# Fuente.net
KiCad netlist of a schematic drawn in EAGLE
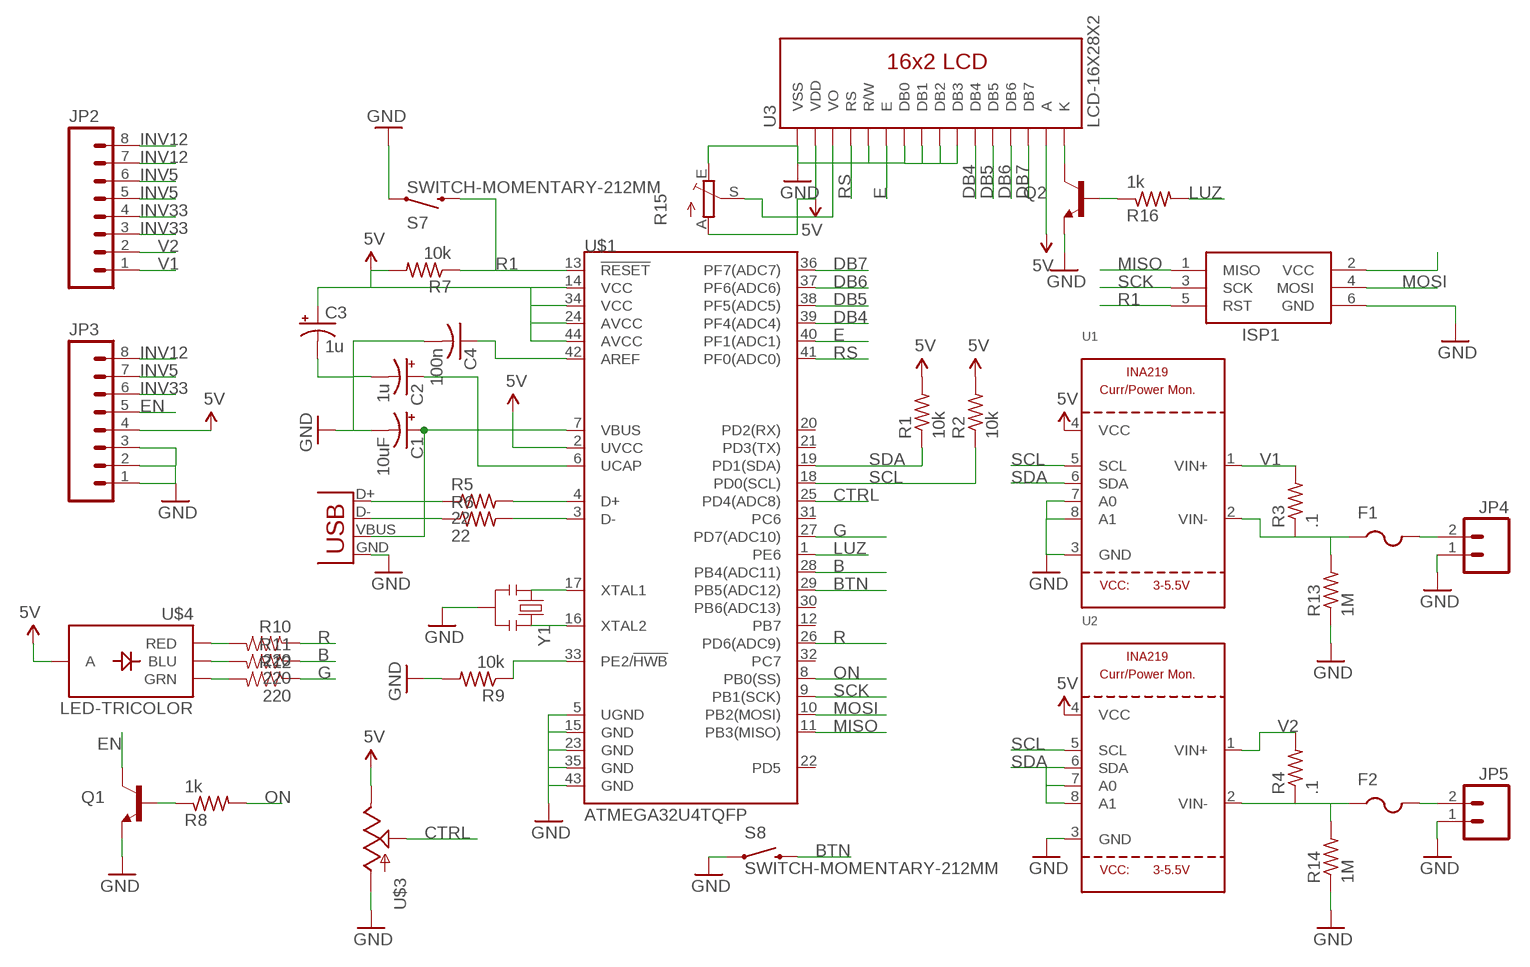
[diagram p0: schematic, sheet 1]

(export (version "E")
  (design (tool "Eeschema 10.0.6"))
  (components
    (comp (ref "C1")
      (value "10uF")
      (footprint "eagle-import:CPOL-RADIAL-10UF-25V")
      (libsource (lib "eagle-import") (part "CAP_POLPTH2"))
    )
    (comp (ref "C2")
      (value "1u")
      (footprint "eagle-import:E2,5-6")
      (libsource (lib "eagle-import") (part "CPOL-USE2.5-6"))
    )
    (comp (ref "C3")
      (value "1u")
      (footprint "eagle-import:E2,5-6")
      (libsource (lib "eagle-import") (part "CPOL-USE2.5-6"))
    )
    (comp (ref "C4")
      (value "100n")
      (footprint "eagle-import:C0805K")
      (libsource (lib "eagle-import") (part "C-USC0805K"))
    )
    (comp (ref "F1")
      (value "PTCFUSE-1812")
      (footprint "eagle-import:1812")
      (libsource (lib "eagle-import") (part "PTCFUSE-1812"))
    )
    (comp (ref "F2")
      (value "PTCFUSE-1812")
      (footprint "eagle-import:1812")
      (libsource (lib "eagle-import") (part "PTCFUSE-1812"))
    )
    (comp (ref "ISP1")
      (value "AVRISP-6")
      (footprint "eagle-import:AVRISP")
      (libsource (lib "eagle-import") (part "AVRISP-6"))
    )
    (comp (ref "JP1")
      (value "USBSMD")
      (footprint "eagle-import:USB-MINIB")
      (libsource (lib "eagle-import") (part "USBSMD"))
    )
    (comp (ref "JP2")
      (value "M08LONGPADS")
      (footprint "eagle-import:1X08_LONGPADS")
      (libsource (lib "eagle-import") (part "M08LONGPADS"))
    )
    (comp (ref "JP3")
      (value "M08LONGPADS")
      (footprint "eagle-import:1X08_LONGPADS")
      (libsource (lib "eagle-import") (part "M08LONGPADS"))
    )
    (comp (ref "JP4")
      (value "M02LOCK_LONGPADS")
      (footprint "eagle-import:1X02_LOCK_LONGPADS")
      (libsource (lib "eagle-import") (part "M02LOCK_LONGPADS"))
    )
    (comp (ref "JP5")
      (value "M02LOCK_LONGPADS")
      (footprint "eagle-import:1X02_LOCK_LONGPADS")
      (libsource (lib "eagle-import") (part "M02LOCK_LONGPADS"))
    )
    (comp (ref "Q1")
      (value "TRANSISTOR_NPNSOT23")
      (footprint "eagle-import:SOT23")
      (libsource (lib "eagle-import") (part "TRANSISTOR_NPNSOT23"))
    )
    (comp (ref "Q2")
      (value "TRANSISTOR_NPNSOT23")
      (footprint "eagle-import:SOT23")
      (libsource (lib "eagle-import") (part "TRANSISTOR_NPNSOT23"))
    )
    (comp (ref "R1")
      (value "10k")
      (footprint "eagle-import:M0805")
      (libsource (lib "eagle-import") (part "R-US_M0805"))
    )
    (comp (ref "R2")
      (value "10k")
      (footprint "eagle-import:M0805")
      (libsource (lib "eagle-import") (part "R-US_M0805"))
    )
    (comp (ref "R3")
      (value ".1")
      (footprint "eagle-import:R2512")
      (libsource (lib "eagle-import") (part "R-US_R2512"))
    )
    (comp (ref "R4")
      (value ".1")
      (footprint "eagle-import:R2512")
      (libsource (lib "eagle-import") (part "R-US_R2512"))
    )
    (comp (ref "R5")
      (value "22")
      (footprint "eagle-import:0309_12")
      (libsource (lib "eagle-import") (part "R-US_0309/12"))
    )
    (comp (ref "R6")
      (value "22")
      (footprint "eagle-import:0309_12")
      (libsource (lib "eagle-import") (part "R-US_0309/12"))
    )
    (comp (ref "R7")
      (value "10k")
      (footprint "eagle-import:M0805")
      (libsource (lib "eagle-import") (part "R-US_M0805"))
    )
    (comp (ref "R8")
      (value "1k")
      (footprint "eagle-import:M0805")
      (libsource (lib "eagle-import") (part "R-US_M0805"))
    )
    (comp (ref "R9")
      (value "10k")
      (footprint "eagle-import:M0805")
      (libsource (lib "eagle-import") (part "R-US_M0805"))
    )
    (comp (ref "R10")
      (value "220")
      (footprint "eagle-import:0805")
      (libsource (lib "eagle-import") (part "RESISTOR0805-RES"))
    )
    (comp (ref "R11")
      (value "220")
      (footprint "eagle-import:0805")
      (libsource (lib "eagle-import") (part "RESISTOR0805-RES"))
    )
    (comp (ref "R12")
      (value "220")
      (footprint "eagle-import:0805")
      (libsource (lib "eagle-import") (part "RESISTOR0805-RES"))
    )
    (comp (ref "R13")
      (value "1M")
      (footprint "eagle-import:M0805")
      (libsource (lib "eagle-import") (part "R-US_M0805"))
    )
    (comp (ref "R14")
      (value "1M")
      (footprint "eagle-import:M0805")
      (libsource (lib "eagle-import") (part "R-US_M0805"))
    )
    (comp (ref "R15")
      (value "TRIM_EU-CT6")
      (footprint "eagle-import:CT6")
      (libsource (lib "eagle-import") (part "TRIM_EU-CT6"))
    )
    (comp (ref "R16")
      (value "1k")
      (footprint "eagle-import:M0805")
      (libsource (lib "eagle-import") (part "R-US_M0805"))
    )
    (comp (ref "S7")
      (value "SWITCH-MOMENTARY-212MM")
      (footprint "eagle-import:TACTILE-PTH-12MM")
      (libsource (lib "eagle-import") (part "SWITCH-MOMENTARY-212MM"))
    )
    (comp (ref "S8")
      (value "SWITCH-MOMENTARY-212MM")
      (footprint "eagle-import:TACTILE-PTH-12MM")
      (libsource (lib "eagle-import") (part "SWITCH-MOMENTARY-212MM"))
    )
    (comp (ref "U$1")
      (value "ATMEGA32U4TQFP")
      (footprint "eagle-import:SPARKFUN-DIGITALIC_TQFP44")
      (libsource (lib "eagle-import") (part "ATMEGA32U4TQFP"))
    )
    (comp (ref "U$3")
      (value "POT-RV16AF-20")
      (footprint "eagle-import:POT_ALPHA_RV16AF-20")
      (libsource (lib "eagle-import") (part "POT-RV16AF-20"))
    )
    (comp (ref "U$4")
      (value "LED-TRICOLOR")
      (footprint "eagle-import:LED-TRICOLOR-SMD")
      (libsource (lib "eagle-import") (part "LED-TRICOLOR"))
    )
    (comp (ref "U1")
      (value "INA219")
      (footprint "eagle-import:SOT23-8")
      (libsource (lib "eagle-import") (part "INA219"))
    )
    (comp (ref "U2")
      (value "INA219")
      (footprint "eagle-import:SOT23-8")
      (libsource (lib "eagle-import") (part "INA219"))
    )
    (comp (ref "U3")
      (value "LCD-16X28X2")
      (footprint "eagle-import:LCD-8X2")
      (libsource (lib "eagle-import") (part "LCD-16X28X2"))
    )
    (comp (ref "Y1")
      (value "RESONATORPTH")
      (footprint "eagle-import:RESONATOR-PTH")
      (libsource (lib "eagle-import") (part "RESONATORPTH"))
    )
  )
  (nets
    (net (code "1") (name "/B") (class "Default")
      (node (ref "R11") (pin "1") (pinfunction "1_1") (pintype "passive"))
      (node (ref "U$1") (pin "28") (pinfunction "PB4(ADC11)_28") (pintype "bidirectional"))
    )
    (net (code "2") (name "/BTN") (class "Default")
      (node (ref "S8") (pin "3") (pinfunction "2_3") (pintype "passive"))
      (node (ref "U$1") (pin "29") (pinfunction "PB5(ADC12)_29") (pintype "bidirectional"))
    )
    (net (code "3") (name "/CTRL") (class "Default")
      (node (ref "U$1") (pin "25") (pinfunction "PD4(ADC8)_25") (pintype "bidirectional"))
      (node (ref "U$3") (pin "2") (pinfunction "S_2") (pintype "passive"))
    )
    (net (code "4") (name "/DB4") (class "Default")
      (node (ref "U$1") (pin "39") (pinfunction "PF4(ADC4)_39") (pintype "bidirectional"))
      (node (ref "U3") (pin "11") (pinfunction "DB4_11") (pintype "bidirectional"))
    )
    (net (code "5") (name "/DB5") (class "Default")
      (node (ref "U$1") (pin "38") (pinfunction "PF5(ADC5)_38") (pintype "bidirectional"))
      (node (ref "U3") (pin "12") (pinfunction "DB5_12") (pintype "bidirectional"))
    )
    (net (code "6") (name "/DB6") (class "Default")
      (node (ref "U$1") (pin "37") (pinfunction "PF6(ADC6)_37") (pintype "bidirectional"))
      (node (ref "U3") (pin "13") (pinfunction "DB6_13") (pintype "bidirectional"))
    )
    (net (code "7") (name "/DB7") (class "Default")
      (node (ref "U$1") (pin "36") (pinfunction "PF7(ADC7)_36") (pintype "bidirectional"))
      (node (ref "U3") (pin "14") (pinfunction "DB7_14") (pintype "bidirectional"))
    )
    (net (code "8") (name "/E") (class "Default")
      (node (ref "U$1") (pin "40") (pinfunction "PF1(ADC1)_40") (pintype "bidirectional"))
      (node (ref "U3") (pin "6") (pinfunction "E_6") (pintype "input"))
    )
    (net (code "9") (name "/EN") (class "Default")
      (node (ref "JP3") (pin "5") (pinfunction "5_5") (pintype "passive"))
      (node (ref "Q1") (pin "3") (pinfunction "C_3") (pintype "passive"))
    )
    (net (code "10") (name "/G") (class "Default")
      (node (ref "R12") (pin "1") (pinfunction "1_1") (pintype "passive"))
      (node (ref "U$1") (pin "27") (pinfunction "PD7(ADC10)_27") (pintype "bidirectional"))
    )
    (net (code "11") (name "/INV5") (class "Default")
      (node (ref "JP2") (pin "5") (pinfunction "5_5") (pintype "passive"))
      (node (ref "JP2") (pin "6") (pinfunction "6_6") (pintype "passive"))
      (node (ref "JP3") (pin "7") (pinfunction "7_7") (pintype "passive"))
    )
    (net (code "12") (name "/INV12") (class "Default")
      (node (ref "JP2") (pin "7") (pinfunction "7_7") (pintype "passive"))
      (node (ref "JP2") (pin "8") (pinfunction "8_8") (pintype "passive"))
      (node (ref "JP3") (pin "8") (pinfunction "8_8") (pintype "passive"))
    )
    (net (code "13") (name "/INV33") (class "Default")
      (node (ref "JP2") (pin "3") (pinfunction "3_3") (pintype "passive"))
      (node (ref "JP2") (pin "4") (pinfunction "4_4") (pintype "passive"))
      (node (ref "JP3") (pin "6") (pinfunction "6_6") (pintype "passive"))
    )
    (net (code "14") (name "/LUZ") (class "Default")
      (node (ref "R16") (pin "2") (pinfunction "2_2") (pintype "passive"))
      (node (ref "U$1") (pin "1") (pinfunction "PE6_1") (pintype "bidirectional"))
    )
    (net (code "15") (name "/MISO") (class "Default")
      (node (ref "ISP1") (pin "1") (pinfunction "MISO_1") (pintype "input"))
      (node (ref "U$1") (pin "11") (pinfunction "PB3(MISO)_11") (pintype "bidirectional"))
    )
    (net (code "16") (name "/MOSI") (class "Default")
      (node (ref "ISP1") (pin "4") (pinfunction "MOSI_4") (pintype "output"))
      (node (ref "U$1") (pin "10") (pinfunction "PB2(MOSI)_10") (pintype "bidirectional"))
    )
    (net (code "17") (name "/ON") (class "Default")
      (node (ref "R8") (pin "2") (pinfunction "2_2") (pintype "passive"))
      (node (ref "U$1") (pin "8") (pinfunction "PB0(SS)_8") (pintype "bidirectional"))
    )
    (net (code "18") (name "/R") (class "Default")
      (node (ref "R10") (pin "1") (pinfunction "1_1") (pintype "passive"))
      (node (ref "U$1") (pin "26") (pinfunction "PD6(ADC9)_26") (pintype "bidirectional"))
    )
    (net (code "19") (name "/R1") (class "Default")
      (node (ref "ISP1") (pin "5") (pinfunction "RST_5") (pintype "output"))
      (node (ref "R7") (pin "1") (pinfunction "1_1") (pintype "passive"))
      (node (ref "S7") (pin "3") (pinfunction "2_3") (pintype "passive"))
      (node (ref "U$1") (pin "13") (pinfunction "~{RESET}_13") (pintype "bidirectional"))
    )
    (net (code "20") (name "/RS") (class "Default")
      (node (ref "U$1") (pin "41") (pinfunction "PF0(ADC0)_41") (pintype "bidirectional"))
      (node (ref "U3") (pin "4") (pinfunction "RS_4") (pintype "input"))
    )
    (net (code "21") (name "/SCK") (class "Default")
      (node (ref "ISP1") (pin "3") (pinfunction "SCK_3") (pintype "output"))
      (node (ref "U$1") (pin "9") (pinfunction "PB1(SCK)_9") (pintype "bidirectional"))
    )
    (net (code "22") (name "/SCL") (class "Default")
      (node (ref "R2") (pin "1") (pinfunction "1_1") (pintype "passive"))
      (node (ref "U$1") (pin "18") (pinfunction "PD0(SCL)_18") (pintype "bidirectional"))
      (node (ref "U1") (pin "5") (pinfunction "SCL_5") (pintype "bidirectional"))
      (node (ref "U2") (pin "5") (pinfunction "SCL_5") (pintype "bidirectional"))
    )
    (net (code "23") (name "/SDA") (class "Default")
      (node (ref "R1") (pin "1") (pinfunction "1_1") (pintype "passive"))
      (node (ref "U$1") (pin "19") (pinfunction "PD1(SDA)_19") (pintype "bidirectional"))
      (node (ref "U1") (pin "6") (pinfunction "SDA_6") (pintype "bidirectional"))
      (node (ref "U2") (pin "6") (pinfunction "SDA_6") (pintype "bidirectional"))
      (node (ref "U2") (pin "7") (pinfunction "A0_7") (pintype "bidirectional"))
      (node (ref "U2") (pin "8") (pinfunction "A1_8") (pintype "bidirectional"))
    )
    (net (code "24") (name "/V1") (class "Default")
      (node (ref "JP2") (pin "1") (pinfunction "1_1") (pintype "passive"))
      (node (ref "R3") (pin "2") (pinfunction "2_2") (pintype "passive"))
      (node (ref "U1") (pin "1") (pinfunction "VIN+_1") (pintype "bidirectional"))
    )
    (net (code "25") (name "/V2") (class "Default")
      (node (ref "JP2") (pin "2") (pinfunction "2_2") (pintype "passive"))
      (node (ref "R4") (pin "2") (pinfunction "2_2") (pintype "passive"))
      (node (ref "U2") (pin "1") (pinfunction "VIN+_1") (pintype "bidirectional"))
    )
    (net (code "26") (name "5V") (class "Default")
      (node (ref "C3") (pin "+") (pinfunction "+_+") (pintype "passive"))
      (node (ref "JP3") (pin "4") (pinfunction "4_4") (pintype "passive"))
      (node (ref "R1") (pin "2") (pinfunction "2_2") (pintype "passive"))
      (node (ref "R15") (pin "A") (pinfunction "A_A") (pintype "passive"))
      (node (ref "R2") (pin "2") (pinfunction "2_2") (pintype "passive"))
      (node (ref "R7") (pin "2") (pinfunction "2_2") (pintype "passive"))
      (node (ref "U$1") (pin "14") (pinfunction "VCC_14") (pintype "bidirectional"))
      (node (ref "U$1") (pin "2") (pinfunction "UVCC_2") (pintype "bidirectional"))
      (node (ref "U$1") (pin "24") (pinfunction "AVCC_24") (pintype "bidirectional"))
      (node (ref "U$1") (pin "34") (pinfunction "VCC_34") (pintype "bidirectional"))
      (node (ref "U$1") (pin "44") (pinfunction "AVCC_44") (pintype "bidirectional"))
      (node (ref "U$3") (pin "3") (pinfunction "E_3") (pintype "passive"))
      (node (ref "U$4") (pin "A") (pinfunction "A_A") (pintype "bidirectional"))
      (node (ref "U1") (pin "4") (pinfunction "VCC_4") (pintype "bidirectional"))
      (node (ref "U2") (pin "4") (pinfunction "VCC_4") (pintype "bidirectional"))
      (node (ref "U3") (pin "15") (pinfunction "A_15") (pintype "power_in"))
      (node (ref "U3") (pin "2") (pinfunction "VDD_2") (pintype "power_in"))
    )
    (net (code "27") (name "GND") (class "Default")
      (node (ref "C1") (pin "2") (pinfunction "-_2") (pintype "passive"))
      (node (ref "C2") (pin "-") (pinfunction "-_-") (pintype "passive"))
      (node (ref "C3") (pin "-") (pinfunction "-_-") (pintype "passive"))
      (node (ref "C4") (pin "2") (pinfunction "2_2") (pintype "passive"))
      (node (ref "ISP1") (pin "6") (pinfunction "GND_6") (pintype "power_in"))
      (node (ref "JP1") (pin "GND") (pinfunction "GND_GND") (pintype "bidirectional"))
      (node (ref "JP3") (pin "1") (pinfunction "1_1") (pintype "passive"))
      (node (ref "JP3") (pin "2") (pinfunction "2_2") (pintype "passive"))
      (node (ref "JP3") (pin "3") (pinfunction "3_3") (pintype "passive"))
      (node (ref "JP4") (pin "1") (pinfunction "1_1") (pintype "passive"))
      (node (ref "JP5") (pin "1") (pinfunction "1_1") (pintype "passive"))
      (node (ref "Q1") (pin "2") (pinfunction "E_2") (pintype "passive"))
      (node (ref "Q2") (pin "2") (pinfunction "E_2") (pintype "passive"))
      (node (ref "R13") (pin "1") (pinfunction "1_1") (pintype "passive"))
      (node (ref "R14") (pin "1") (pinfunction "1_1") (pintype "passive"))
      (node (ref "R15") (pin "E") (pinfunction "E_E") (pintype "passive"))
      (node (ref "R9") (pin "2") (pinfunction "2_2") (pintype "passive"))
      (node (ref "S7") (pin "1") (pinfunction "1_1") (pintype "passive"))
      (node (ref "S8") (pin "1") (pinfunction "1_1") (pintype "passive"))
      (node (ref "U$1") (pin "15") (pinfunction "GND_15") (pintype "bidirectional"))
      (node (ref "U$1") (pin "23") (pinfunction "GND_23") (pintype "bidirectional"))
      (node (ref "U$1") (pin "35") (pinfunction "GND_35") (pintype "bidirectional"))
      (node (ref "U$1") (pin "43") (pinfunction "GND_43") (pintype "bidirectional"))
      (node (ref "U$1") (pin "5") (pinfunction "UGND_5") (pintype "bidirectional"))
      (node (ref "U$3") (pin "1") (pinfunction "A_1") (pintype "passive"))
      (node (ref "U1") (pin "3") (pinfunction "GND_3") (pintype "bidirectional"))
      (node (ref "U1") (pin "7") (pinfunction "A0_7") (pintype "bidirectional"))
      (node (ref "U1") (pin "8") (pinfunction "A1_8") (pintype "bidirectional"))
      (node (ref "U2") (pin "3") (pinfunction "GND_3") (pintype "bidirectional"))
      (node (ref "U3") (pin "1") (pinfunction "VSS_1") (pintype "power_in"))
      (node (ref "U3") (pin "10") (pinfunction "DB3_10") (pintype "bidirectional"))
      (node (ref "U3") (pin "5") (pinfunction "R/W_5") (pintype "input"))
      (node (ref "U3") (pin "7") (pinfunction "DB0_7") (pintype "bidirectional"))
      (node (ref "U3") (pin "8") (pinfunction "DB1_8") (pintype "bidirectional"))
      (node (ref "U3") (pin "9") (pinfunction "DB2_9") (pintype "bidirectional"))
      (node (ref "Y1") (pin "2") (pinfunction "2_2") (pintype "passive"))
    )
    (net (code "28") (name "Net-(C1-+)") (class "Default")
      (node (ref "C1") (pin "1") (pinfunction "+_1") (pintype "passive"))
      (node (ref "JP1") (pin "VBUS") (pinfunction "VBUS_VBUS") (pintype "bidirectional"))
      (node (ref "U$1") (pin "7") (pinfunction "VBUS_7") (pintype "bidirectional"))
    )
    (net (code "29") (name "Net-(F1-Pad2)") (class "Default")
      (node (ref "F1") (pin "2") (pinfunction "2_2") (pintype "passive"))
      (node (ref "JP4") (pin "2") (pinfunction "2_2") (pintype "passive"))
    )
    (net (code "30") (name "Net-(F2-Pad2)") (class "Default")
      (node (ref "F2") (pin "2") (pinfunction "2_2") (pintype "passive"))
      (node (ref "JP5") (pin "2") (pinfunction "2_2") (pintype "passive"))
    )
    (net (code "31") (name "Net-(JP1-PadD+)") (class "Default")
      (node (ref "JP1") (pin "D+") (pinfunction "D+_D+") (pintype "bidirectional"))
      (node (ref "R5") (pin "1") (pinfunction "1_1") (pintype "passive"))
    )
    (net (code "32") (name "Net-(JP1-PadD-)") (class "Default")
      (node (ref "JP1") (pin "D-") (pinfunction "D-_D-") (pintype "bidirectional"))
      (node (ref "R6") (pin "1") (pinfunction "1_1") (pintype "passive"))
    )
    (net (code "33") (name "Net-(Q1-B)") (class "Default")
      (node (ref "Q1") (pin "1") (pinfunction "B_1") (pintype "passive"))
      (node (ref "R8") (pin "1") (pinfunction "1_1") (pintype "passive"))
    )
    (net (code "34") (name "Net-(Q2-B)") (class "Default")
      (node (ref "Q2") (pin "1") (pinfunction "B_1") (pintype "passive"))
      (node (ref "R16") (pin "1") (pinfunction "1_1") (pintype "passive"))
    )
    (net (code "35") (name "Net-(Q2-C)") (class "Default")
      (node (ref "Q2") (pin "3") (pinfunction "C_3") (pintype "passive"))
      (node (ref "U3") (pin "16") (pinfunction "K_16") (pintype "power_in"))
    )
    (net (code "36") (name "Net-(U$1-AREF)") (class "Default")
      (node (ref "C4") (pin "1") (pinfunction "1_1") (pintype "passive"))
      (node (ref "U$1") (pin "42") (pinfunction "AREF_42") (pintype "bidirectional"))
    )
    (net (code "37") (name "Net-(U$1-D+)") (class "Default")
      (node (ref "R5") (pin "2") (pinfunction "2_2") (pintype "passive"))
      (node (ref "U$1") (pin "4") (pinfunction "D+_4") (pintype "bidirectional"))
    )
    (net (code "38") (name "Net-(U$1-D-)") (class "Default")
      (node (ref "R6") (pin "2") (pinfunction "2_2") (pintype "passive"))
      (node (ref "U$1") (pin "3") (pinfunction "D-_3") (pintype "bidirectional"))
    )
    (net (code "39") (name "Net-(U$1-PE2{slash}~{HWB})") (class "Default")
      (node (ref "R9") (pin "1") (pinfunction "1_1") (pintype "passive"))
      (node (ref "U$1") (pin "33") (pinfunction "PE2/~{HWB}_33") (pintype "bidirectional"))
    )
    (net (code "40") (name "Net-(U$1-UCAP)") (class "Default")
      (node (ref "C2") (pin "+") (pinfunction "+_+") (pintype "passive"))
      (node (ref "U$1") (pin "6") (pinfunction "UCAP_6") (pintype "bidirectional"))
    )
    (net (code "41") (name "Net-(U$1-XTAL1)") (class "Default")
      (node (ref "U$1") (pin "17") (pinfunction "XTAL1_17") (pintype "bidirectional"))
      (node (ref "Y1") (pin "1") (pinfunction "1_1") (pintype "passive"))
    )
    (net (code "42") (name "Net-(U$1-XTAL2)") (class "Default")
      (node (ref "U$1") (pin "16") (pinfunction "XTAL2_16") (pintype "bidirectional"))
      (node (ref "Y1") (pin "3") (pinfunction "3_3") (pintype "passive"))
    )
    (net (code "43") (name "Net-(U$4-BLU)") (class "Default")
      (node (ref "R11") (pin "2") (pinfunction "2_2") (pintype "passive"))
      (node (ref "U$4") (pin "B") (pinfunction "BLU_B") (pintype "bidirectional"))
    )
    (net (code "44") (name "Net-(U$4-GRN)") (class "Default")
      (node (ref "R12") (pin "2") (pinfunction "2_2") (pintype "passive"))
      (node (ref "U$4") (pin "G") (pinfunction "GRN_G") (pintype "bidirectional"))
    )
    (net (code "45") (name "Net-(U$4-RED)") (class "Default")
      (node (ref "R10") (pin "2") (pinfunction "2_2") (pintype "passive"))
      (node (ref "U$4") (pin "R") (pinfunction "RED_R") (pintype "bidirectional"))
    )
    (net (code "46") (name "Net-(U1-VIN-)") (class "Default")
      (node (ref "F1") (pin "1") (pinfunction "1_1") (pintype "passive"))
      (node (ref "R13") (pin "2") (pinfunction "2_2") (pintype "passive"))
      (node (ref "R3") (pin "1") (pinfunction "1_1") (pintype "passive"))
      (node (ref "U1") (pin "2") (pinfunction "VIN-_2") (pintype "bidirectional"))
    )
    (net (code "47") (name "Net-(U2-VIN-)") (class "Default")
      (node (ref "F2") (pin "1") (pinfunction "1_1") (pintype "passive"))
      (node (ref "R14") (pin "2") (pinfunction "2_2") (pintype "passive"))
      (node (ref "R4") (pin "1") (pinfunction "1_1") (pintype "passive"))
      (node (ref "U2") (pin "2") (pinfunction "VIN-_2") (pintype "bidirectional"))
    )
    (net (code "48") (name "Net-(U3-VO)") (class "Default")
      (node (ref "R15") (pin "S") (pinfunction "S_S") (pintype "passive"))
      (node (ref "U3") (pin "3") (pinfunction "VO_3") (pintype "bidirectional"))
    )
    (net (code "49") (name "unconnected-(ISP1-VCC-Pad2)") (class "Default")
      (node (ref "ISP1") (pin "2") (pinfunction "VCC_2") (pintype "power_in"))
    )
    (net (code "50") (name "unconnected-(U$1-PB6(ADC13)-Pad30)") (class "Default")
      (node (ref "U$1") (pin "30") (pinfunction "PB6(ADC13)_30") (pintype "bidirectional"))
    )
    (net (code "51") (name "unconnected-(U$1-PB7-Pad12)") (class "Default")
      (node (ref "U$1") (pin "12") (pinfunction "PB7_12") (pintype "bidirectional"))
    )
    (net (code "52") (name "unconnected-(U$1-PC6-Pad31)") (class "Default")
      (node (ref "U$1") (pin "31") (pinfunction "PC6_31") (pintype "bidirectional"))
    )
    (net (code "53") (name "unconnected-(U$1-PC7-Pad32)") (class "Default")
      (node (ref "U$1") (pin "32") (pinfunction "PC7_32") (pintype "bidirectional"))
    )
    (net (code "54") (name "unconnected-(U$1-PD2(RX)-Pad20)") (class "Default")
      (node (ref "U$1") (pin "20") (pinfunction "PD2(RX)_20") (pintype "bidirectional"))
    )
    (net (code "55") (name "unconnected-(U$1-PD3(TX)-Pad21)") (class "Default")
      (node (ref "U$1") (pin "21") (pinfunction "PD3(TX)_21") (pintype "bidirectional"))
    )
    (net (code "56") (name "unconnected-(U$1-PD5-Pad22)") (class "Default")
      (node (ref "U$1") (pin "22") (pinfunction "PD5_22") (pintype "bidirectional"))
    )
  )
)
